# Testboard_1_2.net
KiCad netlist of a schematic drawn in EAGLE
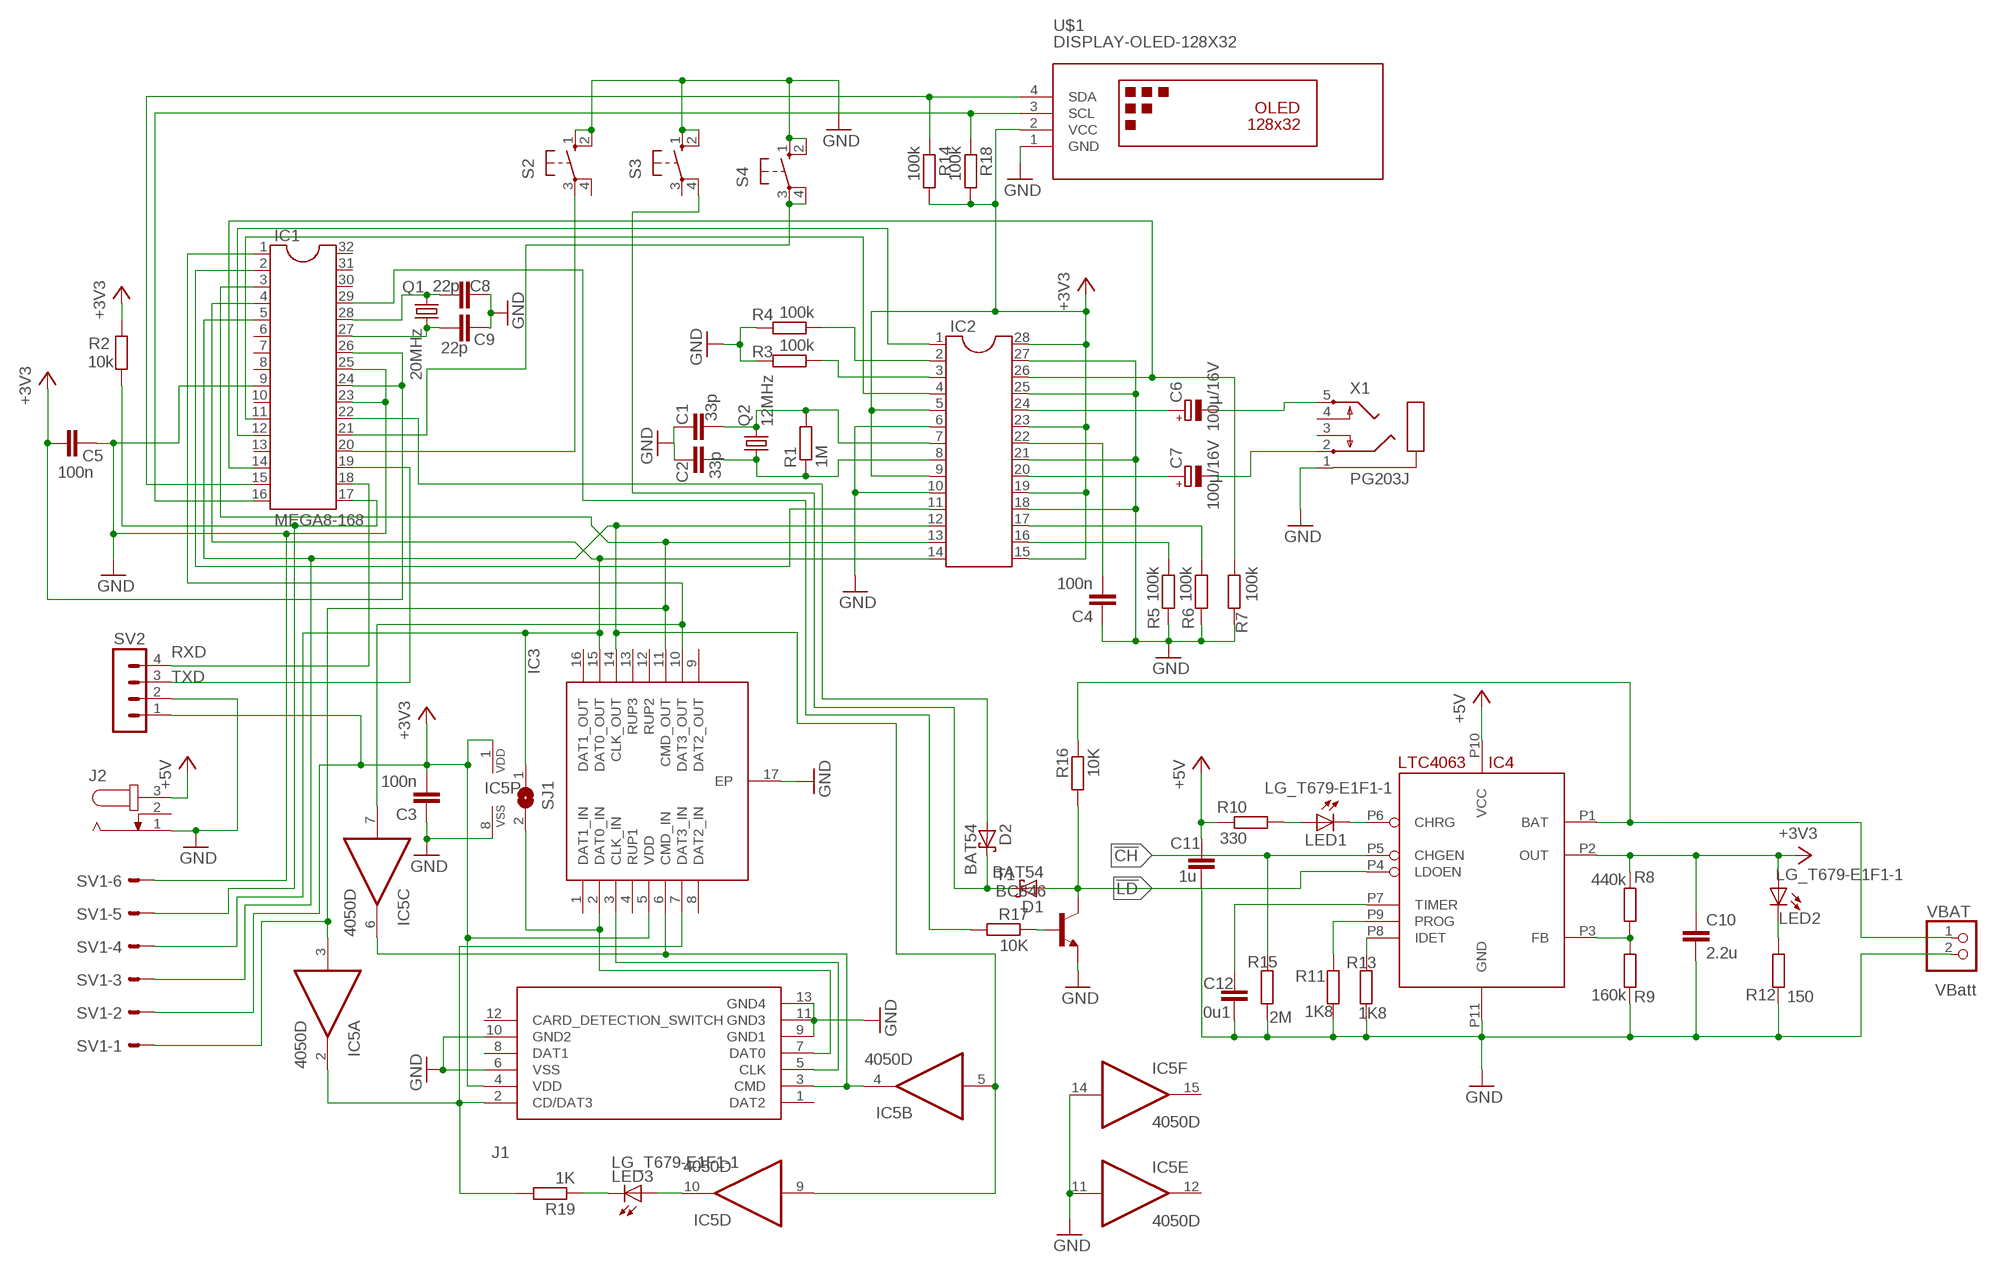
[diagram p0: schematic, sheet 1]

(export (version "E")
  (design (tool "Eeschema 10.0.6"))
  (components
    (comp (ref "C1")
      (value "33p")
      (footprint "eagle-import:C1206K")
      (libsource (lib "eagle-import") (part "C-EUC1206K"))
    )
    (comp (ref "C2")
      (value "33p")
      (footprint "eagle-import:C1206K")
      (libsource (lib "eagle-import") (part "C-EUC1206K"))
    )
    (comp (ref "C3")
      (value "100n")
      (footprint "eagle-import:C1206K")
      (libsource (lib "eagle-import") (part "C-EUC1206K"))
    )
    (comp (ref "C4")
      (value "100n")
      (footprint "eagle-import:C1206K")
      (libsource (lib "eagle-import") (part "C-EUC1206K"))
    )
    (comp (ref "C5")
      (value "100n")
      (footprint "eagle-import:C1206K")
      (libsource (lib "eagle-import") (part "C-EUC1206K"))
    )
    (comp (ref "C6")
      (value "100µ/16V")
      (footprint "eagle-import:UD-6,3X7,7_NICHICON")
      (libsource (lib "eagle-import") (part "CPOL-EUUD-6,3X7,7"))
    )
    (comp (ref "C7")
      (value "100µ/16V")
      (footprint "eagle-import:UD-6,3X7,7_NICHICON")
      (libsource (lib "eagle-import") (part "CPOL-EUUD-6,3X7,7"))
    )
    (comp (ref "C8")
      (value "22p")
      (footprint "eagle-import:C1206K")
      (libsource (lib "eagle-import") (part "rcl_334_C-EUC1206K"))
    )
    (comp (ref "C9")
      (value "22p")
      (footprint "eagle-import:C1206K")
      (libsource (lib "eagle-import") (part "rcl_334_C-EUC1206K"))
    )
    (comp (ref "C10")
      (value "2.2u")
      (footprint "eagle-import:C0805K")
      (libsource (lib "eagle-import") (part "C-EUC0805K"))
    )
    (comp (ref "C11")
      (value "1u")
      (footprint "eagle-import:C0805K")
      (libsource (lib "eagle-import") (part "C-EUC0805K"))
    )
    (comp (ref "C12")
      (value "0u1")
      (footprint "eagle-import:C0805K")
      (libsource (lib "eagle-import") (part "C-EUC0805K"))
    )
    (comp (ref "D1")
      (value "BAT54")
      (footprint "eagle-import:SOT23")
      (libsource (lib "eagle-import") (part "BAT54"))
    )
    (comp (ref "D2")
      (value "BAT54")
      (footprint "eagle-import:SOT23")
      (libsource (lib "eagle-import") (part "BAT54"))
    )
    (comp (ref "IC1")
      (value "MEGA8-168")
      (footprint "eagle-import:DIL32")
      (libsource (lib "eagle-import") (part "DIL32"))
    )
    (comp (ref "IC2")
      (value "DIL28-3")
      (footprint "eagle-import:DIL28-3")
      (libsource (lib "eagle-import") (part "DIL28-3"))
    )
    (comp (ref "IC3")
      (value "ECLAMP2410P.TCT")
      (footprint "eagle-import:SON50P160X400X65-17N")
      (fields (field (name "RS_PART_NUMBER") "6910638"))
      (libsource (lib "eagle-import") (part "ECLAMP2410P.TCT"))
    )
    (comp (ref "IC4")
      (value "LTC4063")
      (footprint "eagle-import:LTC4063")
      (libsource (lib "eagle-import") (part "LTC4063"))
    )
    (comp (ref "IC5")
      (value "4050D")
      (footprint "eagle-import:SO16")
      (libsource (lib "eagle-import") (part "4050D"))
    )
    (comp (ref "J1")
      (value "DM3CS-SF")
      (footprint "eagle-import:DM3CS-SF")
      (fields (field (name "RS_PART_NUMBER") "1664833"))
      (libsource (lib "eagle-import") (part "DM3CS-SF"))
    )
    (comp (ref "J2")
      (value "JACK-PLUG0")
      (footprint "eagle-import:SPC4077")
      (libsource (lib "eagle-import") (part "JACK-PLUG0"))
    )
    (comp (ref "LED1")
      (value "LG_T679-E1F1-1")
      (footprint "eagle-import:LED5MM")
      (libsource (lib "eagle-import") (part "LED5MM"))
    )
    (comp (ref "LED2")
      (value "LG_T679-E1F1-1")
      (footprint "eagle-import:LED5MM")
      (libsource (lib "eagle-import") (part "LED5MM"))
    )
    (comp (ref "LED3")
      (value "LG_T679-E1F1-1")
      (footprint "eagle-import:LED5MM")
      (libsource (lib "eagle-import") (part "LED5MM"))
    )
    (comp (ref "Q1")
      (value "20MHz")
      (footprint "eagle-import:HC49UP")
      (libsource (lib "eagle-import") (part "crystal_204_CRYSTALHC49UP"))
    )
    (comp (ref "Q2")
      (value "12MHz")
      (footprint "eagle-import:HC49UP")
      (libsource (lib "eagle-import") (part "CRYSTALHC49UP"))
    )
    (comp (ref "R1")
      (value "1M")
      (footprint "eagle-import:R0805")
      (libsource (lib "eagle-import") (part "rcl_334_R-EU_R0805"))
    )
    (comp (ref "R2")
      (value "10k")
      (footprint "eagle-import:0207_10")
      (libsource (lib "eagle-import") (part "rcl_334_R-EU_0207/10"))
    )
    (comp (ref "R3")
      (value "100k")
      (footprint "eagle-import:R1206")
      (libsource (lib "eagle-import") (part "rcl_334_R-EU_R1206"))
    )
    (comp (ref "R4")
      (value "100k")
      (footprint "eagle-import:R1206")
      (libsource (lib "eagle-import") (part "rcl_334_R-EU_R1206"))
    )
    (comp (ref "R5")
      (value "100k")
      (footprint "eagle-import:R0805")
      (libsource (lib "eagle-import") (part "rcl_334_R-EU_R0805"))
    )
    (comp (ref "R6")
      (value "100k")
      (footprint "eagle-import:R0805")
      (libsource (lib "eagle-import") (part "rcl_334_R-EU_R0805"))
    )
    (comp (ref "R7")
      (value "100k")
      (footprint "eagle-import:R1206")
      (libsource (lib "eagle-import") (part "rcl_334_R-EU_R1206"))
    )
    (comp (ref "R8")
      (value "440k")
      (footprint "eagle-import:R0805")
      (libsource (lib "eagle-import") (part "rcl_334_R-EU_R0805"))
    )
    (comp (ref "R9")
      (value "160k")
      (footprint "eagle-import:R0805")
      (libsource (lib "eagle-import") (part "rcl_334_R-EU_R0805"))
    )
    (comp (ref "R10")
      (value "330")
      (footprint "eagle-import:R0805")
      (libsource (lib "eagle-import") (part "rcl_334_R-EU_R0805"))
    )
    (comp (ref "R11")
      (value "1K8")
      (footprint "eagle-import:R0805")
      (libsource (lib "eagle-import") (part "R-EU_R0805"))
    )
    (comp (ref "R12")
      (value "150")
      (footprint "eagle-import:R0805")
      (libsource (lib "eagle-import") (part "rcl_334_R-EU_R0805"))
    )
    (comp (ref "R13")
      (value "1K8")
      (footprint "eagle-import:R1206")
      (libsource (lib "eagle-import") (part "rcl_334_R-EU_R1206"))
    )
    (comp (ref "R14")
      (value "100k")
      (footprint "eagle-import:0207_10")
      (libsource (lib "eagle-import") (part "rcl_334_R-EU_0207/10"))
    )
    (comp (ref "R15")
      (value "2M")
      (footprint "eagle-import:R0805")
      (libsource (lib "eagle-import") (part "rcl_334_R-EU_R0805"))
    )
    (comp (ref "R16")
      (value "10K")
      (footprint "eagle-import:0207_10")
      (libsource (lib "eagle-import") (part "rcl_334_R-EU_0207/10"))
    )
    (comp (ref "R17")
      (value "10K")
      (footprint "eagle-import:0207_10")
      (libsource (lib "eagle-import") (part "rcl_334_R-EU_0207/10"))
    )
    (comp (ref "R18")
      (value "100k")
      (footprint "eagle-import:0207_10")
      (libsource (lib "eagle-import") (part "rcl_334_R-EU_0207/10"))
    )
    (comp (ref "R19")
      (value "1K")
      (footprint "eagle-import:0207_10")
      (libsource (lib "eagle-import") (part "rcl_334_R-EU_0207/10"))
    )
    (comp (ref "S2")
      (value "10-XX")
      (footprint "eagle-import:B3F-10XX")
      (fields (field (name "MPN") "B3F-1000"))
      (libsource (lib "eagle-import") (part "10-XX"))
    )
    (comp (ref "S3")
      (value "10-XX")
      (footprint "eagle-import:B3F-10XX")
      (fields (field (name "MPN") "B3F-1000"))
      (libsource (lib "eagle-import") (part "10-XX"))
    )
    (comp (ref "S4")
      (value "10-XX")
      (footprint "eagle-import:B3F-10XX")
      (fields (field (name "MPN") "B3F-1000"))
      (libsource (lib "eagle-import") (part "10-XX"))
    )
    (comp (ref "SJ1") (value "SJ") (footprint "eagle-import:SJ") (libsource (lib "eagle-import") (part "SJ")))
    (comp (ref "SV1")
      (value "ML6E")
      (footprint "eagle-import:ML6")
      (libsource (lib "eagle-import") (part "ML6E"))
    )
    (comp (ref "SV2")
      (value "MA04-1")
      (footprint "eagle-import:MA04-1")
      (libsource (lib "eagle-import") (part "MA04-1"))
    )
    (comp (ref "T1")
      (value "BC846")
      (footprint "eagle-import:SOT23")
      (libsource (lib "eagle-import") (part "BC846"))
    )
    (comp (ref "U$1")
      (value "DISPLAY-OLED-128X32")
      (footprint "eagle-import:DISPLAY-OLED-128X32")
      (libsource (lib "eagle-import") (part "DISPLAY-OLED-128X32"))
    )
    (comp (ref "VBAT")
      (value "PINHD-1X2")
      (footprint "eagle-import:1X02")
      (libsource (lib "eagle-import") (part "PINHD-1X2"))
    )
    (comp (ref "X1")
      (value "PG203J")
      (footprint "eagle-import:PG203J")
      (libsource (lib "eagle-import") (part "PG203J"))
    )
  )
  (nets
    (net (code "1") (name "+3V3") (class "Default")
      (node (ref "C10") (pin "1") (pinfunction "1_1") (pintype "passive"))
      (node (ref "C3") (pin "2") (pinfunction "2_2") (pintype "passive"))
      (node (ref "C5") (pin "2") (pinfunction "2_2") (pintype "passive"))
      (node (ref "IC1") (pin "24") (pinfunction "24_24") (pintype "passive"))
      (node (ref "IC1") (pin "26") (pinfunction "26_26") (pintype "passive"))
      (node (ref "IC2") (pin "15") (pinfunction "15_15") (pintype "passive"))
      (node (ref "IC2") (pin "19") (pinfunction "19_19") (pintype "passive"))
      (node (ref "IC2") (pin "23") (pinfunction "23_23") (pintype "passive"))
      (node (ref "IC2") (pin "28") (pinfunction "28_28") (pintype "passive"))
      (node (ref "IC2") (pin "5") (pinfunction "5_5") (pintype "passive"))
      (node (ref "IC2") (pin "9") (pinfunction "9_9") (pintype "passive"))
      (node (ref "IC3") (pin "5") (pinfunction "VDD_5") (pintype "bidirectional"))
      (node (ref "IC4") (pin "P2") (pinfunction "OUT_P2") (pintype "output"))
      (node (ref "IC5") (pin "1") (pinfunction "VDD_1") (pintype "power_in"))
      (node (ref "J1") (pin "4") (pinfunction "VDD_4") (pintype "bidirectional"))
      (node (ref "LED2") (pin "A") (pinfunction "A_A") (pintype "passive"))
      (node (ref "R14") (pin "2") (pinfunction "2_2") (pintype "passive"))
      (node (ref "R18") (pin "2") (pinfunction "2_2") (pintype "passive"))
      (node (ref "R2") (pin "2") (pinfunction "2_2") (pintype "passive"))
      (node (ref "R8") (pin "2") (pinfunction "2_2") (pintype "passive"))
      (node (ref "SV1") (pin "2") (pinfunction "S_2") (pintype "passive"))
      (node (ref "SV2") (pin "1") (pinfunction "1_1") (pintype "passive"))
      (node (ref "U$1") (pin "2") (pinfunction "VCC_2") (pintype "power_in"))
    )
    (net (code "2") (name "+5V") (class "Default")
      (node (ref "C11") (pin "1") (pinfunction "1_1") (pintype "passive"))
      (node (ref "IC4") (pin "P10") (pinfunction "VCC_P10") (pintype "power_in"))
      (node (ref "J2") (pin "3") (pinfunction "3_3") (pintype "passive"))
      (node (ref "R10") (pin "2") (pinfunction "2_2") (pintype "passive"))
    )
    (net (code "3") (name "/~{CH}") (class "Default")
      (node (ref "IC4") (pin "P5") (pinfunction "CHGEN_P5") (pintype "input"))
      (node (ref "R15") (pin "2") (pinfunction "2_2") (pintype "passive"))
    )
    (net (code "4") (name "/~{LD}") (class "Default")
      (node (ref "D1") (pin "1") (pinfunction "A_1") (pintype "passive"))
      (node (ref "IC4") (pin "P4") (pinfunction "LDOEN_P4") (pintype "input"))
      (node (ref "R16") (pin "2") (pinfunction "2_2") (pintype "passive"))
      (node (ref "T1") (pin "3") (pinfunction "C_3") (pintype "passive"))
    )
    (net (code "5") (name "GND") (class "Default")
      (node (ref "C1") (pin "1") (pinfunction "1_1") (pintype "passive"))
      (node (ref "C10") (pin "2") (pinfunction "2_2") (pintype "passive"))
      (node (ref "C11") (pin "2") (pinfunction "2_2") (pintype "passive"))
      (node (ref "C12") (pin "2") (pinfunction "2_2") (pintype "passive"))
      (node (ref "C2") (pin "1") (pinfunction "1_1") (pintype "passive"))
      (node (ref "C3") (pin "1") (pinfunction "1_1") (pintype "passive"))
      (node (ref "C4") (pin "1") (pinfunction "1_1") (pintype "passive"))
      (node (ref "C5") (pin "1") (pinfunction "1_1") (pintype "passive"))
      (node (ref "C8") (pin "1") (pinfunction "1_1") (pintype "passive"))
      (node (ref "C9") (pin "1") (pinfunction "1_1") (pintype "passive"))
      (node (ref "IC1") (pin "23") (pinfunction "23_23") (pintype "passive"))
      (node (ref "IC1") (pin "25") (pinfunction "25_25") (pintype "passive"))
      (node (ref "IC1") (pin "9") (pinfunction "9_9") (pintype "passive"))
      (node (ref "IC2") (pin "10") (pinfunction "10_10") (pintype "passive"))
      (node (ref "IC2") (pin "18") (pinfunction "18_18") (pintype "passive"))
      (node (ref "IC2") (pin "21") (pinfunction "21_21") (pintype "passive"))
      (node (ref "IC2") (pin "25") (pinfunction "25_25") (pintype "passive"))
      (node (ref "IC2") (pin "27") (pinfunction "27_27") (pintype "passive"))
      (node (ref "IC2") (pin "6") (pinfunction "6_6") (pintype "passive"))
      (node (ref "IC3") (pin "17") (pinfunction "EP_17") (pintype "bidirectional"))
      (node (ref "IC4") (pin "P11") (pinfunction "GND_P11") (pintype "power_in"))
      (node (ref "IC5") (pin "11") (pinfunction "I_11") (pintype "input"))
      (node (ref "IC5") (pin "14") (pinfunction "I_14") (pintype "input"))
      (node (ref "IC5") (pin "8") (pinfunction "VSS_8") (pintype "power_in"))
      (node (ref "J1") (pin "10") (pinfunction "GND2_10") (pintype "bidirectional"))
      (node (ref "J1") (pin "11") (pinfunction "GND3_11") (pintype "bidirectional"))
      (node (ref "J1") (pin "13") (pinfunction "GND4_13") (pintype "bidirectional"))
      (node (ref "J1") (pin "6") (pinfunction "VSS_6") (pintype "bidirectional"))
      (node (ref "J1") (pin "9") (pinfunction "GND1_9") (pintype "bidirectional"))
      (node (ref "J2") (pin "1") (pinfunction "1_1") (pintype "passive"))
      (node (ref "R11") (pin "1") (pinfunction "1_1") (pintype "passive"))
      (node (ref "R12") (pin "2") (pinfunction "2_2") (pintype "passive"))
      (node (ref "R13") (pin "1") (pinfunction "1_1") (pintype "passive"))
      (node (ref "R15") (pin "1") (pinfunction "1_1") (pintype "passive"))
      (node (ref "R3") (pin "2") (pinfunction "2_2") (pintype "passive"))
      (node (ref "R4") (pin "2") (pinfunction "2_2") (pintype "passive"))
      (node (ref "R5") (pin "2") (pinfunction "2_2") (pintype "passive"))
      (node (ref "R6") (pin "2") (pinfunction "2_2") (pintype "passive"))
      (node (ref "R7") (pin "2") (pinfunction "2_2") (pintype "passive"))
      (node (ref "R9") (pin "1") (pinfunction "1_1") (pintype "passive"))
      (node (ref "S2") (pin "1") (pinfunction "S_1") (pintype "passive"))
      (node (ref "S2") (pin "2") (pinfunction "S1_2") (pintype "passive"))
      (node (ref "S3") (pin "1") (pinfunction "S_1") (pintype "passive"))
      (node (ref "S3") (pin "2") (pinfunction "S1_2") (pintype "passive"))
      (node (ref "S4") (pin "1") (pinfunction "S_1") (pintype "passive"))
      (node (ref "S4") (pin "2") (pinfunction "S1_2") (pintype "passive"))
      (node (ref "SV1") (pin "6") (pinfunction "S_6") (pintype "passive"))
      (node (ref "SV2") (pin "2") (pinfunction "2_2") (pintype "passive"))
      (node (ref "T1") (pin "2") (pinfunction "E_2") (pintype "passive"))
      (node (ref "U$1") (pin "1") (pinfunction "GND_1") (pintype "power_in"))
      (node (ref "VBAT") (pin "2") (pinfunction "2_2") (pintype "passive"))
      (node (ref "X1") (pin "1") (pinfunction "1_1") (pintype "passive"))
    )
    (net (code "6") (name "Net-(C1-Pad2)") (class "Default")
      (node (ref "C1") (pin "2") (pinfunction "2_2") (pintype "passive"))
      (node (ref "IC2") (pin "7") (pinfunction "7_7") (pintype "passive"))
      (node (ref "Q2") (pin "2") (pinfunction "2_2") (pintype "passive"))
      (node (ref "R1") (pin "2") (pinfunction "2_2") (pintype "passive"))
    )
    (net (code "7") (name "Net-(C2-Pad2)") (class "Default")
      (node (ref "C2") (pin "2") (pinfunction "2_2") (pintype "passive"))
      (node (ref "IC2") (pin "8") (pinfunction "8_8") (pintype "passive"))
      (node (ref "Q2") (pin "1") (pinfunction "1_1") (pintype "passive"))
      (node (ref "R1") (pin "1") (pinfunction "1_1") (pintype "passive"))
    )
    (net (code "8") (name "Net-(C4-Pad2)") (class "Default")
      (node (ref "C4") (pin "2") (pinfunction "2_2") (pintype "passive"))
      (node (ref "IC2") (pin "22") (pinfunction "22_22") (pintype "passive"))
    )
    (net (code "9") (name "Net-(C6-Pad+)") (class "Default")
      (node (ref "C6") (pin "+") (pinfunction "+_+") (pintype "passive"))
      (node (ref "IC2") (pin "24") (pinfunction "24_24") (pintype "passive"))
    )
    (net (code "10") (name "Net-(C6-Pad-)") (class "Default")
      (node (ref "C6") (pin "-") (pinfunction "-_-") (pintype "passive"))
      (node (ref "X1") (pin "5") (pinfunction "5_5") (pintype "passive"))
    )
    (net (code "11") (name "Net-(C7-Pad+)") (class "Default")
      (node (ref "C7") (pin "+") (pinfunction "+_+") (pintype "passive"))
      (node (ref "IC2") (pin "20") (pinfunction "20_20") (pintype "passive"))
    )
    (net (code "12") (name "Net-(C7-Pad-)") (class "Default")
      (node (ref "C7") (pin "-") (pinfunction "-_-") (pintype "passive"))
      (node (ref "X1") (pin "2") (pinfunction "2_2") (pintype "passive"))
    )
    (net (code "13") (name "Net-(C8-Pad2)") (class "Default")
      (node (ref "C8") (pin "2") (pinfunction "2_2") (pintype "passive"))
      (node (ref "IC1") (pin "28") (pinfunction "28_28") (pintype "passive"))
      (node (ref "Q1") (pin "1") (pinfunction "1_1") (pintype "passive"))
    )
    (net (code "14") (name "Net-(C9-Pad2)") (class "Default")
      (node (ref "C9") (pin "2") (pinfunction "2_2") (pintype "passive"))
      (node (ref "IC1") (pin "27") (pinfunction "27_27") (pintype "passive"))
      (node (ref "Q1") (pin "2") (pinfunction "2_2") (pintype "passive"))
    )
    (net (code "15") (name "Net-(D1-C)") (class "Default")
      (node (ref "D1") (pin "3") (pinfunction "C_3") (pintype "passive"))
      (node (ref "D2") (pin "3") (pinfunction "C_3") (pintype "passive"))
      (node (ref "S3") (pin "4") (pinfunction "P1_4") (pintype "passive"))
    )
    (net (code "16") (name "Net-(D2-A)") (class "Default")
      (node (ref "D2") (pin "1") (pinfunction "A_1") (pintype "passive"))
      (node (ref "IC1") (pin "22") (pinfunction "22_22") (pintype "passive"))
    )
    (net (code "17") (name "Net-(IC1-Pad2)") (class "Default")
      (node (ref "IC1") (pin "2") (pinfunction "2_2") (pintype "passive"))
      (node (ref "IC2") (pin "11") (pinfunction "11_11") (pintype "passive"))
    )
    (net (code "18") (name "Net-(IC1-Pad11)") (class "Default")
      (node (ref "IC1") (pin "11") (pinfunction "11_11") (pintype "passive"))
      (node (ref "IC2") (pin "4") (pinfunction "4_4") (pintype "passive"))
    )
    (net (code "19") (name "Net-(IC1-Pad12)") (class "Default")
      (node (ref "IC1") (pin "12") (pinfunction "12_12") (pintype "passive"))
      (node (ref "IC2") (pin "1") (pinfunction "1_1") (pintype "passive"))
    )
    (net (code "20") (name "Net-(IC1-Pad14)") (class "Default")
      (node (ref "IC1") (pin "14") (pinfunction "14_14") (pintype "passive"))
      (node (ref "IC2") (pin "26") (pinfunction "26_26") (pintype "passive"))
      (node (ref "R7") (pin "1") (pinfunction "1_1") (pintype "passive"))
    )
    (net (code "21") (name "Net-(IC1-Pad18)") (class "Default")
      (node (ref "IC1") (pin "18") (pinfunction "18_18") (pintype "passive"))
      (node (ref "SV2") (pin "4") (pinfunction "4_4") (pintype "passive"))
    )
    (net (code "22") (name "Net-(IC1-Pad19)") (class "Default")
      (node (ref "IC1") (pin "19") (pinfunction "19_19") (pintype "passive"))
      (node (ref "SV2") (pin "3") (pinfunction "3_3") (pintype "passive"))
    )
    (net (code "23") (name "Net-(IC1-Pad29)") (class "Default")
      (node (ref "IC1") (pin "29") (pinfunction "29_29") (pintype "passive"))
      (node (ref "R17") (pin "2") (pinfunction "2_2") (pintype "passive"))
    )
    (net (code "24") (name "Net-(IC2-Pad2)") (class "Default")
      (node (ref "IC2") (pin "2") (pinfunction "2_2") (pintype "passive"))
      (node (ref "R4") (pin "1") (pinfunction "1_1") (pintype "passive"))
    )
    (net (code "25") (name "Net-(IC2-Pad3)") (class "Default")
      (node (ref "IC2") (pin "3") (pinfunction "3_3") (pintype "passive"))
      (node (ref "R3") (pin "1") (pinfunction "1_1") (pintype "passive"))
    )
    (net (code "26") (name "Net-(IC2-Pad16)") (class "Default")
      (node (ref "IC2") (pin "16") (pinfunction "16_16") (pintype "passive"))
      (node (ref "R5") (pin "1") (pinfunction "1_1") (pintype "passive"))
    )
    (net (code "27") (name "Net-(IC2-Pad17)") (class "Default")
      (node (ref "IC2") (pin "17") (pinfunction "17_17") (pintype "passive"))
      (node (ref "R6") (pin "1") (pinfunction "1_1") (pintype "passive"))
    )
    (net (code "28") (name "Net-(IC3-CLK_IN)") (class "Default")
      (node (ref "IC3") (pin "3") (pinfunction "CLK_IN_3") (pintype "bidirectional"))
      (node (ref "J1") (pin "5") (pinfunction "CLK_5") (pintype "bidirectional"))
    )
    (net (code "29") (name "Net-(IC3-CLK_OUT)") (class "Default")
      (node (ref "IC1") (pin "5") (pinfunction "5_5") (pintype "passive"))
      (node (ref "IC2") (pin "12") (pinfunction "12_12") (pintype "passive"))
      (node (ref "IC3") (pin "14") (pinfunction "CLK_OUT_14") (pintype "bidirectional"))
      (node (ref "IC5") (pin "5") (pinfunction "I_5") (pintype "input"))
      (node (ref "IC5") (pin "9") (pinfunction "I_9") (pintype "input"))
      (node (ref "SV1") (pin "3") (pinfunction "S_3") (pintype "passive"))
    )
    (net (code "30") (name "Net-(IC3-CMD_IN)") (class "Default")
      (node (ref "IC3") (pin "6") (pinfunction "CMD_IN_6") (pintype "bidirectional"))
      (node (ref "IC5") (pin "4") (pinfunction "O_4") (pintype "output"))
      (node (ref "IC5") (pin "6") (pinfunction "O_6") (pintype "output"))
      (node (ref "J1") (pin "3") (pinfunction "CMD_3") (pintype "bidirectional"))
    )
    (net (code "31") (name "Net-(IC3-CMD_OUT)") (class "Default")
      (node (ref "IC1") (pin "3") (pinfunction "3_3") (pintype "passive"))
      (node (ref "IC2") (pin "13") (pinfunction "13_13") (pintype "passive"))
      (node (ref "IC3") (pin "11") (pinfunction "CMD_OUT_11") (pintype "bidirectional"))
      (node (ref "IC5") (pin "3") (pinfunction "I_3") (pintype "input"))
      (node (ref "SV1") (pin "1") (pinfunction "S_1") (pintype "passive"))
    )
    (net (code "32") (name "Net-(IC3-DAT0_IN)") (class "Default")
      (node (ref "IC3") (pin "2") (pinfunction "DAT0_IN_2") (pintype "bidirectional"))
      (node (ref "J1") (pin "7") (pinfunction "DAT0_7") (pintype "bidirectional"))
      (node (ref "SJ1") (pin "2") (pinfunction "2_2") (pintype "passive"))
    )
    (net (code "33") (name "Net-(IC3-DAT0_OUT)") (class "Default")
      (node (ref "IC1") (pin "4") (pinfunction "4_4") (pintype "passive"))
      (node (ref "IC2") (pin "14") (pinfunction "14_14") (pintype "passive"))
      (node (ref "IC3") (pin "15") (pinfunction "DAT0_OUT_15") (pintype "bidirectional"))
      (node (ref "SJ1") (pin "1") (pinfunction "1_1") (pintype "passive"))
      (node (ref "SV1") (pin "4") (pinfunction "S_4") (pintype "passive"))
    )
    (net (code "34") (name "Net-(IC3-DAT3_IN)") (class "Default")
      (node (ref "IC3") (pin "7") (pinfunction "DAT3_IN_7") (pintype "bidirectional"))
      (node (ref "IC5") (pin "2") (pinfunction "O_2") (pintype "output"))
      (node (ref "J1") (pin "2") (pinfunction "CD/DAT3_2") (pintype "bidirectional"))
      (node (ref "R19") (pin "2") (pinfunction "2_2") (pintype "passive"))
    )
    (net (code "35") (name "Net-(IC3-DAT3_OUT)") (class "Default")
      (node (ref "IC1") (pin "1") (pinfunction "1_1") (pintype "passive"))
      (node (ref "IC3") (pin "10") (pinfunction "DAT3_OUT_10") (pintype "bidirectional"))
      (node (ref "IC5") (pin "7") (pinfunction "I_7") (pintype "input"))
    )
    (net (code "36") (name "Net-(IC4-BAT)") (class "Default")
      (node (ref "IC4") (pin "P1") (pinfunction "BAT_P1") (pintype "output"))
      (node (ref "R16") (pin "1") (pinfunction "1_1") (pintype "passive"))
      (node (ref "VBAT") (pin "1") (pinfunction "1_1") (pintype "passive"))
    )
    (net (code "37") (name "Net-(IC4-CHRG)") (class "Default")
      (node (ref "IC4") (pin "P6") (pinfunction "CHRG_P6") (pintype "output"))
      (node (ref "LED1") (pin "K") (pinfunction "C_K") (pintype "passive"))
    )
    (net (code "38") (name "Net-(IC4-FB)") (class "Default")
      (node (ref "IC4") (pin "P3") (pinfunction "FB_P3") (pintype "passive"))
      (node (ref "R8") (pin "1") (pinfunction "1_1") (pintype "passive"))
      (node (ref "R9") (pin "2") (pinfunction "2_2") (pintype "passive"))
    )
    (net (code "39") (name "Net-(IC4-IDET)") (class "Default")
      (node (ref "IC4") (pin "P8") (pinfunction "IDET_P8") (pintype "passive"))
      (node (ref "R13") (pin "2") (pinfunction "2_2") (pintype "passive"))
    )
    (net (code "40") (name "Net-(IC4-PROG)") (class "Default")
      (node (ref "IC4") (pin "P9") (pinfunction "PROG_P9") (pintype "passive"))
      (node (ref "R11") (pin "2") (pinfunction "2_2") (pintype "passive"))
    )
    (net (code "41") (name "Net-(IC4-TIMER)") (class "Default")
      (node (ref "C12") (pin "1") (pinfunction "1_1") (pintype "passive"))
      (node (ref "IC4") (pin "P7") (pinfunction "TIMER_P7") (pintype "passive"))
    )
    (net (code "42") (name "Net-(IC5D-O)") (class "Default")
      (node (ref "IC5") (pin "10") (pinfunction "O_10") (pintype "output"))
      (node (ref "LED3") (pin "A") (pinfunction "A_A") (pintype "passive"))
    )
    (net (code "43") (name "Net-(LED1-PadA)") (class "Default")
      (node (ref "LED1") (pin "A") (pinfunction "A_A") (pintype "passive"))
      (node (ref "R10") (pin "1") (pinfunction "1_1") (pintype "passive"))
    )
    (net (code "44") (name "Net-(LED2-C)") (class "Default")
      (node (ref "LED2") (pin "K") (pinfunction "C_K") (pintype "passive"))
      (node (ref "R12") (pin "1") (pinfunction "1_1") (pintype "passive"))
    )
    (net (code "45") (name "Net-(LED3-C)") (class "Default")
      (node (ref "LED3") (pin "K") (pinfunction "C_K") (pintype "passive"))
      (node (ref "R19") (pin "1") (pinfunction "1_1") (pintype "passive"))
    )
    (net (code "46") (name "Net-(S2-P)") (class "Default")
      (node (ref "IC1") (pin "20") (pinfunction "20_20") (pintype "passive"))
      (node (ref "S2") (pin "3") (pinfunction "P_3") (pintype "passive"))
    )
    (net (code "47") (name "Net-(S4-P)") (class "Default")
      (node (ref "IC1") (pin "21") (pinfunction "21_21") (pintype "passive"))
      (node (ref "S4") (pin "3") (pinfunction "P_3") (pintype "passive"))
      (node (ref "S4") (pin "4") (pinfunction "P1_4") (pintype "passive"))
    )
    (net (code "48") (name "Net-(SV1E-S)") (class "Default")
      (node (ref "IC1") (pin "17") (pinfunction "17_17") (pintype "passive"))
      (node (ref "R2") (pin "1") (pinfunction "1_1") (pintype "passive"))
      (node (ref "SV1") (pin "5") (pinfunction "S_5") (pintype "passive"))
    )
    (net (code "49") (name "Net-(T1-B)") (class "Default")
      (node (ref "R17") (pin "1") (pinfunction "1_1") (pintype "passive"))
      (node (ref "T1") (pin "1") (pinfunction "B_1") (pintype "passive"))
    )
    (net (code "50") (name "Net-(U$1-SCL)") (class "Default")
      (node (ref "IC1") (pin "16") (pinfunction "16_16") (pintype "passive"))
      (node (ref "R18") (pin "1") (pinfunction "1_1") (pintype "passive"))
      (node (ref "U$1") (pin "3") (pinfunction "SCL_3") (pintype "bidirectional"))
    )
    (net (code "51") (name "Net-(U$1-SDA)") (class "Default")
      (node (ref "IC1") (pin "15") (pinfunction "15_15") (pintype "passive"))
      (node (ref "R14") (pin "1") (pinfunction "1_1") (pintype "passive"))
      (node (ref "U$1") (pin "4") (pinfunction "SDA_4") (pintype "bidirectional"))
    )
    (net (code "52") (name "unconnected-(IC1-Pad6)") (class "Default")
      (node (ref "IC1") (pin "6") (pinfunction "6_6") (pintype "passive"))
    )
    (net (code "53") (name "unconnected-(IC1-Pad7)") (class "Default")
      (node (ref "IC1") (pin "7") (pinfunction "7_7") (pintype "passive"))
    )
    (net (code "54") (name "unconnected-(IC1-Pad8)") (class "Default")
      (node (ref "IC1") (pin "8") (pinfunction "8_8") (pintype "passive"))
    )
    (net (code "55") (name "unconnected-(IC1-Pad10)") (class "Default")
      (node (ref "IC1") (pin "10") (pinfunction "10_10") (pintype "passive"))
    )
    (net (code "56") (name "unconnected-(IC1-Pad13)") (class "Default")
      (node (ref "IC1") (pin "13") (pinfunction "13_13") (pintype "passive"))
    )
    (net (code "57") (name "unconnected-(IC1-Pad30)") (class "Default")
      (node (ref "IC1") (pin "30") (pinfunction "30_30") (pintype "passive"))
    )
    (net (code "58") (name "unconnected-(IC1-Pad31)") (class "Default")
      (node (ref "IC1") (pin "31") (pinfunction "31_31") (pintype "passive"))
    )
    (net (code "59") (name "unconnected-(IC1-Pad32)") (class "Default")
      (node (ref "IC1") (pin "32") (pinfunction "32_32") (pintype "passive"))
    )
    (net (code "60") (name "unconnected-(IC3-DAT1_IN-Pad1)") (class "Default")
      (node (ref "IC3") (pin "1") (pinfunction "DAT1_IN_1") (pintype "bidirectional"))
    )
    (net (code "61") (name "unconnected-(IC3-DAT1_OUT-Pad16)") (class "Default")
      (node (ref "IC3") (pin "16") (pinfunction "DAT1_OUT_16") (pintype "bidirectional"))
    )
    (net (code "62") (name "unconnected-(IC3-DAT2_IN-Pad8)") (class "Default")
      (node (ref "IC3") (pin "8") (pinfunction "DAT2_IN_8") (pintype "bidirectional"))
    )
    (net (code "63") (name "unconnected-(IC3-DAT2_OUT-Pad9)") (class "Default")
      (node (ref "IC3") (pin "9") (pinfunction "DAT2_OUT_9") (pintype "bidirectional"))
    )
    (net (code "64") (name "unconnected-(IC3-RUP1-Pad4)") (class "Default")
      (node (ref "IC3") (pin "4") (pinfunction "RUP1_4") (pintype "bidirectional"))
    )
    (net (code "65") (name "unconnected-(IC3-RUP2-Pad12)") (class "Default")
      (node (ref "IC3") (pin "12") (pinfunction "RUP2_12") (pintype "bidirectional"))
    )
    (net (code "66") (name "unconnected-(IC3-RUP3-Pad13)") (class "Default")
      (node (ref "IC3") (pin "13") (pinfunction "RUP3_13") (pintype "bidirectional"))
    )
    (net (code "67") (name "unconnected-(IC5E-O-Pad12)") (class "Default")
      (node (ref "IC5") (pin "12") (pinfunction "O_12") (pintype "output"))
    )
    (net (code "68") (name "unconnected-(IC5F-O-Pad15)") (class "Default")
      (node (ref "IC5") (pin "15") (pinfunction "O_15") (pintype "output"))
    )
    (net (code "69") (name "unconnected-(J1-CARD_DETECTION_SWITCH-Pad12)") (class "Default")
      (node (ref "J1") (pin "12") (pinfunction "CARD_DETECTION_SWITCH_12") (pintype "bidirectional"))
    )
    (net (code "70") (name "unconnected-(J1-DAT1-Pad8)") (class "Default")
      (node (ref "J1") (pin "8") (pinfunction "DAT1_8") (pintype "bidirectional"))
    )
    (net (code "71") (name "unconnected-(J1-DAT2-Pad1)") (class "Default")
      (node (ref "J1") (pin "1") (pinfunction "DAT2_1") (pintype "bidirectional"))
    )
    (net (code "72") (name "unconnected-(J2-Pad2)") (class "Default")
      (node (ref "J2") (pin "2") (pinfunction "2_2") (pintype "passive"))
    )
    (net (code "73") (name "unconnected-(S2-P1-Pad4)") (class "Default")
      (node (ref "S2") (pin "4") (pinfunction "P1_4") (pintype "passive"))
    )
    (net (code "74") (name "unconnected-(S3-P-Pad3)") (class "Default")
      (node (ref "S3") (pin "3") (pinfunction "P_3") (pintype "passive"))
    )
    (net (code "75") (name "unconnected-(X1-Pad3)") (class "Default")
      (node (ref "X1") (pin "3") (pinfunction "3_3") (pintype "passive"))
    )
    (net (code "76") (name "unconnected-(X1-Pad4)") (class "Default")
      (node (ref "X1") (pin "4") (pinfunction "4_4") (pintype "passive"))
    )
  )
)
